# TMP.net
KiCad netlist of a schematic drawn in EAGLE
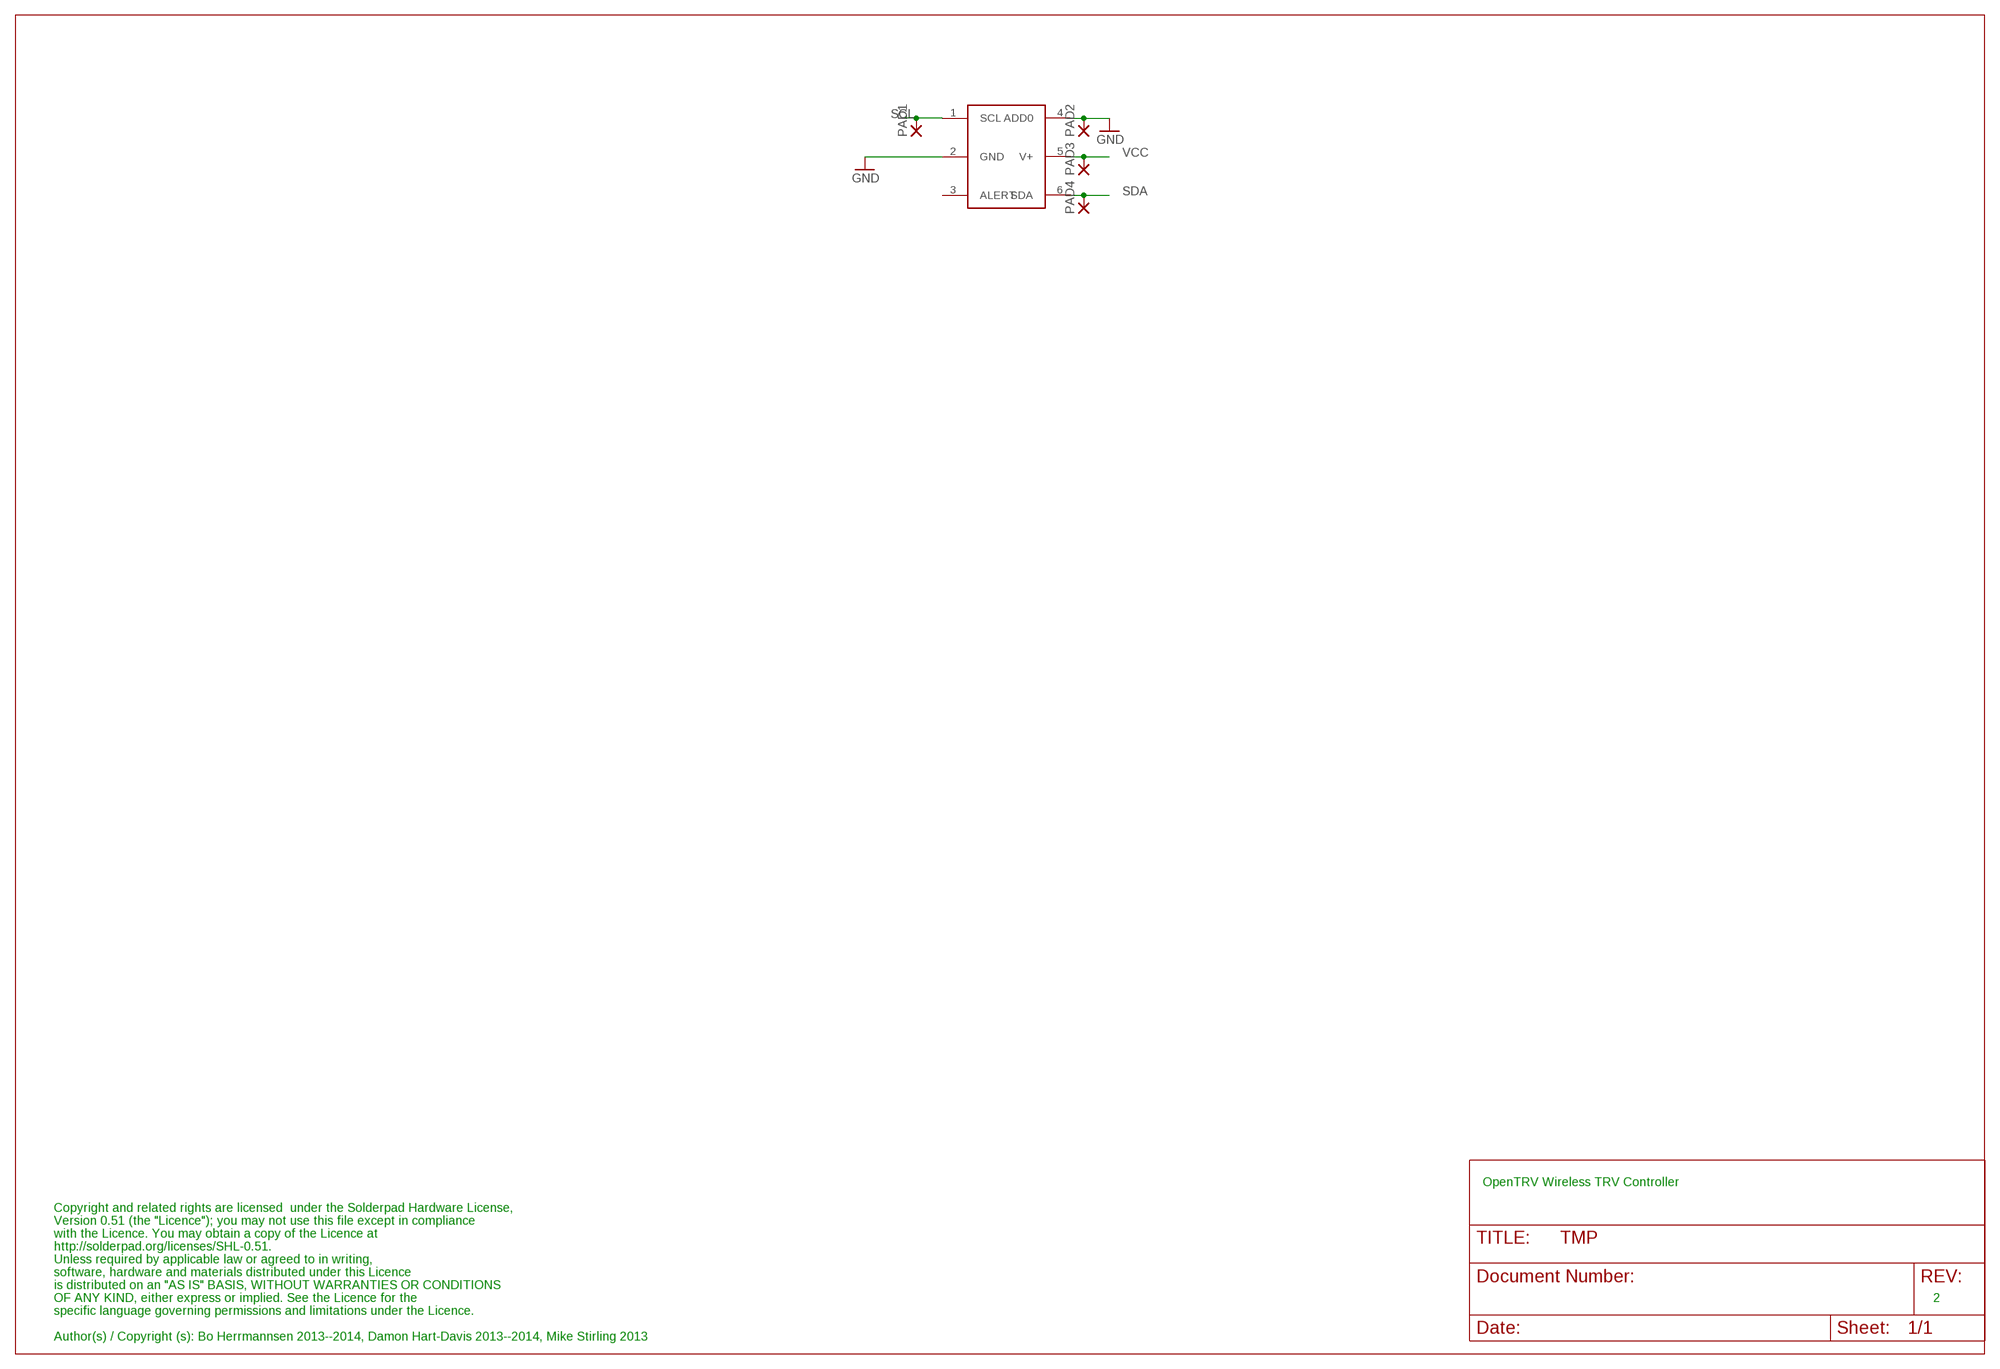
[diagram p0: schematic, sheet 1]

(export (version "E")
  (design (tool "Eeschema 10.0.6"))
  (components
    (comp (ref "PAD1")
      (value "1,6/0,8")
      (footprint "eagle-import:1,6_0,8")
      (libsource (lib "eagle-import") (part "1,6/0,8"))
    )
    (comp (ref "PAD2")
      (value "1,6/0,8")
      (footprint "eagle-import:1,6_0,8")
      (libsource (lib "eagle-import") (part "1,6/0,8"))
    )
    (comp (ref "PAD3")
      (value "1,6/0,8")
      (footprint "eagle-import:1,6_0,8")
      (libsource (lib "eagle-import") (part "1,6/0,8"))
    )
    (comp (ref "PAD4")
      (value "1,6/0,8")
      (footprint "eagle-import:1,6_0,8")
      (libsource (lib "eagle-import") (part "1,6/0,8"))
    )
    (comp (ref "TMP1")
      (value "TMP1")
      (footprint "eagle-import:TMP112")
      (libsource (lib "eagle-import") (part "TMP112"))
    )
  )
  (nets
    (net (code "1") (name "/SCL") (class "Default")
      (node (ref "PAD1") (pin "1") (pinfunction "P_1") (pintype "passive"))
      (node (ref "TMP1") (pin "1") (pinfunction "SCL_1") (pintype "bidirectional"))
    )
    (net (code "2") (name "/SDA") (class "Default")
      (node (ref "PAD4") (pin "1") (pinfunction "P_1") (pintype "passive"))
      (node (ref "TMP1") (pin "6") (pinfunction "SDA_6") (pintype "bidirectional"))
    )
    (net (code "3") (name "/VCC") (class "Default")
      (node (ref "PAD3") (pin "1") (pinfunction "P_1") (pintype "passive"))
      (node (ref "TMP1") (pin "5") (pinfunction "V+_5") (pintype "bidirectional"))
    )
    (net (code "4") (name "GND") (class "Default")
      (node (ref "PAD2") (pin "1") (pinfunction "P_1") (pintype "passive"))
      (node (ref "TMP1") (pin "2") (pinfunction "GND_2") (pintype "bidirectional"))
      (node (ref "TMP1") (pin "4") (pinfunction "ADD0_4") (pintype "bidirectional"))
    )
    (net (code "5") (name "unconnected-(TMP1-ALERT-Pad3)") (class "Default")
      (node (ref "TMP1") (pin "3") (pinfunction "ALERT_3") (pintype "bidirectional"))
    )
  )
)
